# zook.net
KiCad netlist of a schematic drawn in EAGLE
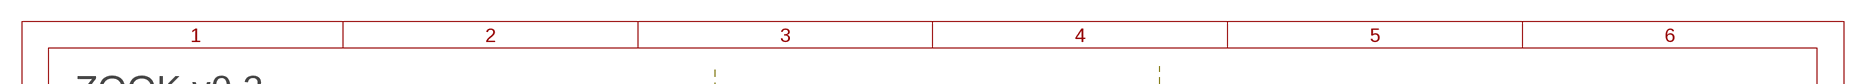
[diagram p0: schematic, sheet 1, part 1 of 2]
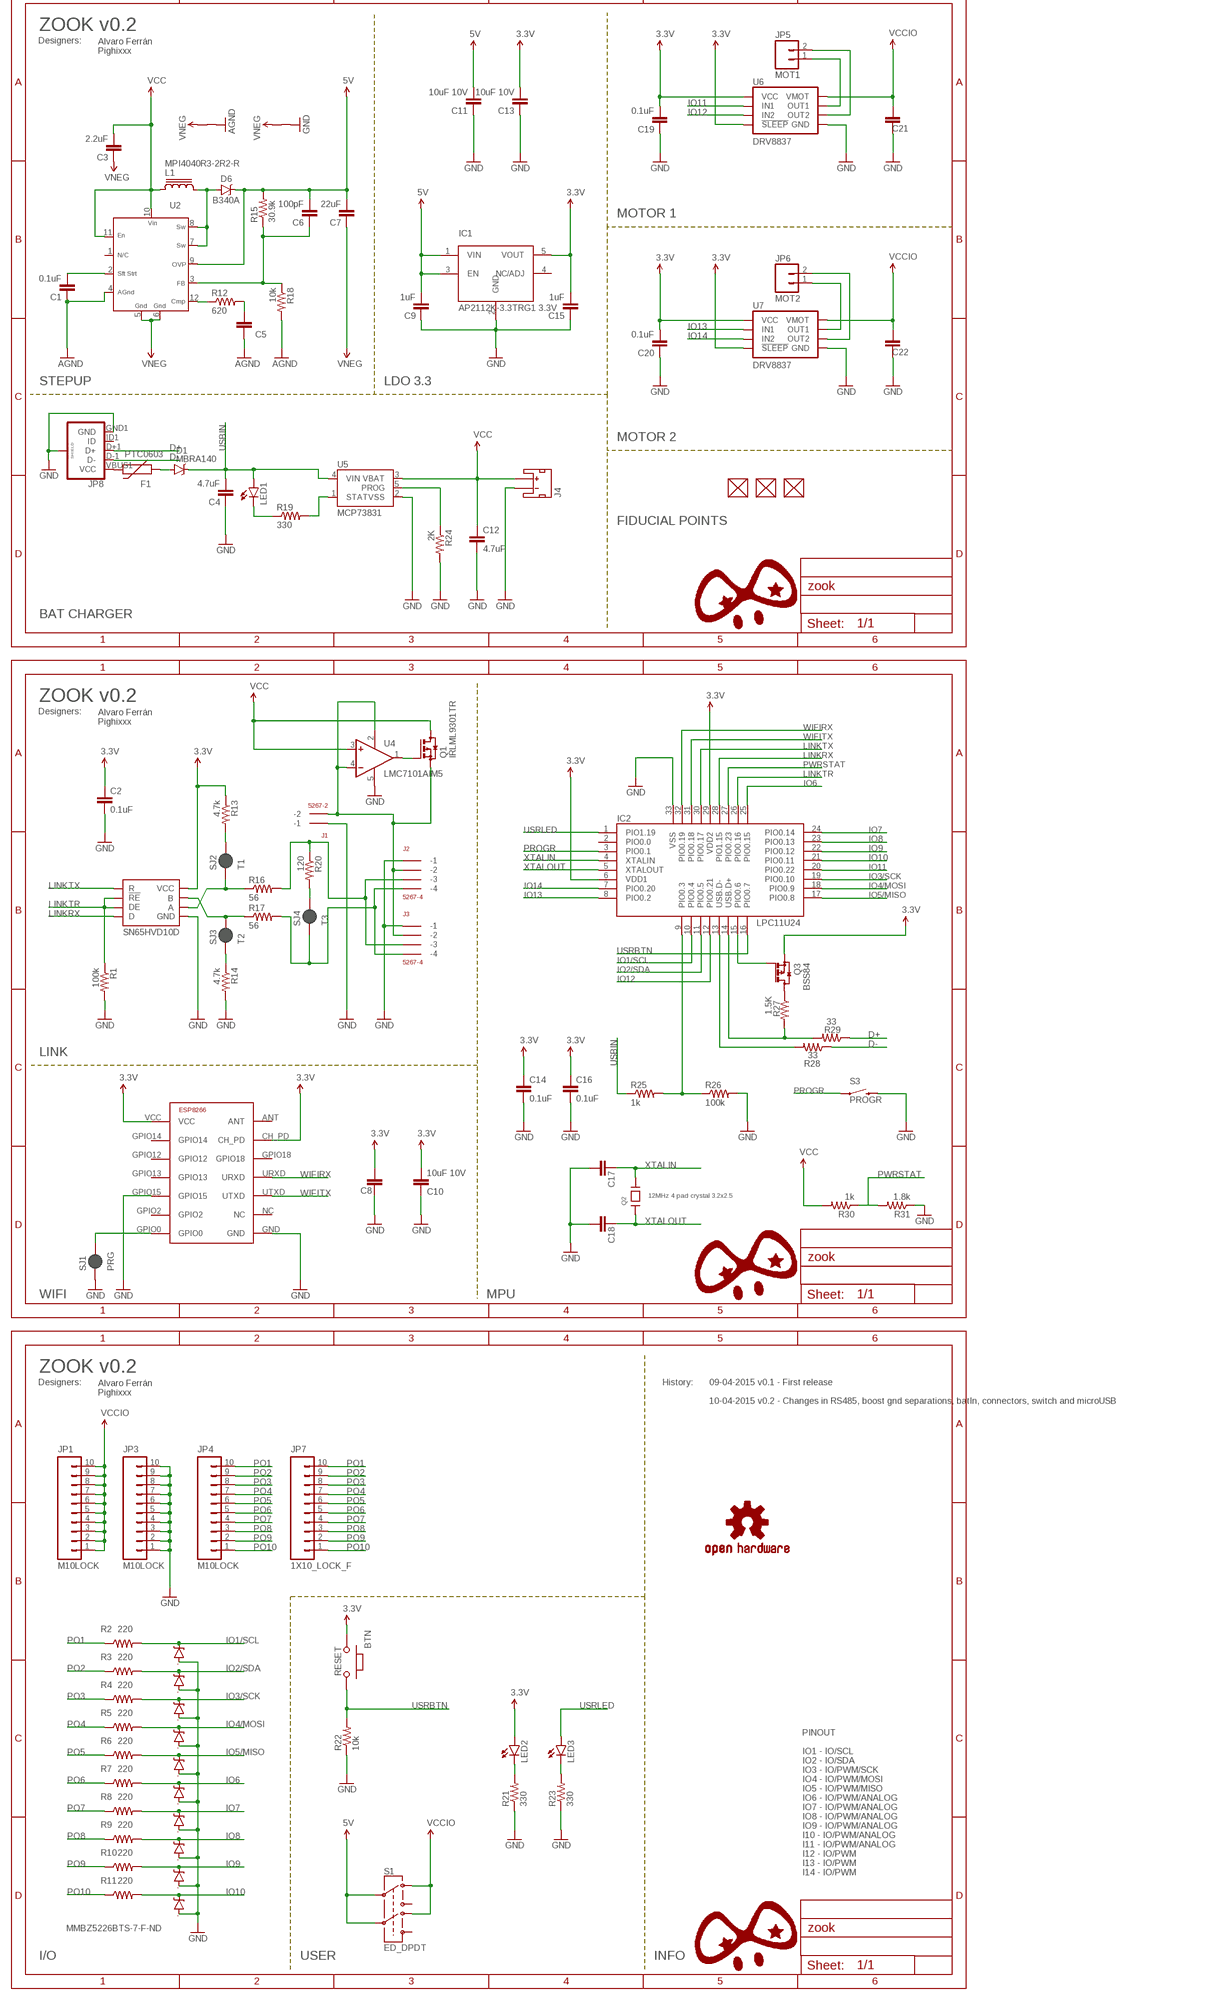
[diagram p1: schematic, sheet 1, part 2 of 2]

(export (version "E")
  (design (tool "Eeschema 10.0.6"))
  (components
    (comp (ref "BTN")
      (value "RESET")
      (footprint "eagle-import:157SW")
      (libsource (lib "eagle-import") (part "PB157"))
    )
    (comp (ref "C1")
      (value "0.1uF")
      (footprint "eagle-import:0402-CAP")
      (libsource (lib "eagle-import") (part "CAP0402-CAP"))
    )
    (comp (ref "C2")
      (value "0.1uF")
      (footprint "eagle-import:0402-CAP")
      (libsource (lib "eagle-import") (part "CAP0402-CAP"))
    )
    (comp (ref "C3")
      (value "2.2uF")
      (footprint "eagle-import:0402-CAP")
      (libsource (lib "eagle-import") (part "CAP0402-CAP"))
    )
    (comp (ref "C4")
      (value "4.7uF")
      (footprint "eagle-import:0402-CAP")
      (libsource (lib "eagle-import") (part "CAP0402-CAP"))
    )
    (comp (ref "C5")
      (value "10nF")
      (footprint "eagle-import:0402-CAP")
      (libsource (lib "eagle-import") (part "CAP0402-CAP"))
    )
    (comp (ref "C6")
      (value "100pF")
      (footprint "eagle-import:0402-CAP")
      (libsource (lib "eagle-import") (part "CAP0402-CAP"))
    )
    (comp (ref "C7")
      (value "22uF")
      (footprint "eagle-import:0805")
      (libsource (lib "eagle-import") (part "22UF-6.3V-20%(0805)"))
    )
    (comp (ref "C8")
      (value "0.1uF")
      (footprint "eagle-import:0402-CAP")
      (libsource (lib "eagle-import") (part "CAP0402-CAP"))
    )
    (comp (ref "C9")
      (value "1uF")
      (footprint "eagle-import:0402-CAP")
      (libsource (lib "eagle-import") (part "CAP0402-CAP"))
    )
    (comp (ref "C10")
      (value "10uF 10V")
      (footprint "eagle-import:0402-CAP")
      (libsource (lib "eagle-import") (part "CAP0402-CAP"))
    )
    (comp (ref "C11")
      (value "10uF 10V")
      (footprint "eagle-import:0402-CAP")
      (libsource (lib "eagle-import") (part "CAP0402-CAP"))
    )
    (comp (ref "C12")
      (value "4.7uF")
      (footprint "eagle-import:0402-CAP")
      (libsource (lib "eagle-import") (part "CAP0402-CAP"))
    )
    (comp (ref "C13")
      (value "10uF 10V")
      (footprint "eagle-import:0402-CAP")
      (libsource (lib "eagle-import") (part "CAP0402-CAP"))
    )
    (comp (ref "C14")
      (value "0.1uF")
      (footprint "eagle-import:0402-CAP")
      (libsource (lib "eagle-import") (part "CAP0402-CAP"))
    )
    (comp (ref "C15")
      (value "1uF")
      (footprint "eagle-import:0402-CAP")
      (libsource (lib "eagle-import") (part "CAP0402-CAP"))
    )
    (comp (ref "C16")
      (value "0.1uF")
      (footprint "eagle-import:0402-CAP")
      (libsource (lib "eagle-import") (part "CAP0402-CAP"))
    )
    (comp (ref "C17")
      (value "27pF")
      (footprint "eagle-import:0402-CAP")
      (libsource (lib "eagle-import") (part "CAP0402-CAP"))
    )
    (comp (ref "C18")
      (value "27pF")
      (footprint "eagle-import:0402-CAP")
      (libsource (lib "eagle-import") (part "CAP0402-CAP"))
    )
    (comp (ref "C19")
      (value "0.1uF")
      (footprint "eagle-import:0402-CAP")
      (libsource (lib "eagle-import") (part "CAP0402-CAP"))
    )
    (comp (ref "C20")
      (value "0.1uF")
      (footprint "eagle-import:0402-CAP")
      (libsource (lib "eagle-import") (part "CAP0402-CAP"))
    )
    (comp (ref "C21")
      (value "0.1uF")
      (footprint "eagle-import:0402-CAP")
      (libsource (lib "eagle-import") (part "CAP0402-CAP"))
    )
    (comp (ref "C22")
      (value "0.1uF")
      (footprint "eagle-import:0402-CAP")
      (libsource (lib "eagle-import") (part "CAP0402-CAP"))
    )
    (comp (ref "D1")
      (value "MBRA140")
      (footprint "eagle-import:SMA-DIODE")
      (libsource (lib "eagle-import") (part "MBRA140"))
    )
    (comp (ref "D2")
      (value "ZENERARRAY")
      (footprint "eagle-import:SOT363")
      (libsource (lib "eagle-import") (part "ZENERARRAY"))
    )
    (comp (ref "D3")
      (value "ZENERARRAY")
      (footprint "eagle-import:SOT363")
      (libsource (lib "eagle-import") (part "ZENERARRAY"))
    )
    (comp (ref "D4")
      (value "ZENERARRAY")
      (footprint "eagle-import:SOT363")
      (libsource (lib "eagle-import") (part "ZENERARRAY"))
    )
    (comp (ref "D5")
      (value "ZENERARRAY")
      (footprint "eagle-import:SOT363")
      (libsource (lib "eagle-import") (part "ZENERARRAY"))
    )
    (comp (ref "D6")
      (value "B340A")
      (footprint "eagle-import:SMA-DIODE")
      (libsource (lib "eagle-import") (part "DIODE-SCHOTTKY-B340A"))
    )
    (comp (ref "F1")
      (value "PTC0603")
      (footprint "eagle-import:0603")
      (libsource (lib "eagle-import") (part "PTC0603"))
    )
    (comp (ref "FUD1")
      (value "FIDUCIAL")
      (footprint "eagle-import:FIDUCIAL_40MIL")
      (libsource (lib "eagle-import") (part "FIDUCIAL"))
    )
    (comp (ref "FUD2")
      (value "FIDUCIAL")
      (footprint "eagle-import:FIDUCIAL_40MIL")
      (libsource (lib "eagle-import") (part "FIDUCIAL"))
    )
    (comp (ref "FUD3")
      (value "FIDUCIAL")
      (footprint "eagle-import:FIDUCIAL_40MIL")
      (libsource (lib "eagle-import") (part "FIDUCIAL"))
    )
    (comp (ref "GND5")
      (value "VIRTUAL_GND")
      (footprint "eagle-import:STARGND")
      (libsource (lib "eagle-import") (part "VIRTUAL_GND"))
    )
    (comp (ref "GND6")
      (value "VIRTUAL_GND")
      (footprint "eagle-import:STARGND")
      (libsource (lib "eagle-import") (part "VIRTUAL_GND"))
    )
    (comp (ref "IC1")
      (value "AP2112K-3.3TRG1 3.3V")
      (footprint "eagle-import:SOT23-5")
      (libsource (lib "eagle-import") (part "5PIN_REG"))
    )
    (comp (ref "IC2")
      (value "LPC11U24")
      (footprint "eagle-import:HVQFN33_5X5MM")
      (libsource (lib "eagle-import") (part "LPC11U2X_HVQFN33(5X5)"))
    )
    (comp (ref "J1")
      (value "5267-2")
      (footprint "eagle-import:5267-2")
      (libsource (lib "eagle-import") (part "5267-2"))
    )
    (comp (ref "J2")
      (value "5267-4")
      (footprint "eagle-import:5267-4")
      (libsource (lib "eagle-import") (part "5267-4"))
    )
    (comp (ref "J3")
      (value "5267-4")
      (footprint "eagle-import:5267-4")
      (libsource (lib "eagle-import") (part "5267-4"))
    )
    (comp (ref "J4")
      (value "BATT")
      (footprint "eagle-import:JST-2-SMD")
      (libsource (lib "eagle-import") (part "JST_2MM_MALE"))
    )
    (comp (ref "JP1")
      (value "M10LOCK")
      (footprint "eagle-import:1X10_LOCK")
      (libsource (lib "eagle-import") (part "M10LOCK"))
    )
    (comp (ref "JP3")
      (value "M10LOCK")
      (footprint "eagle-import:1X10_LOCK")
      (libsource (lib "eagle-import") (part "M10LOCK"))
    )
    (comp (ref "JP4")
      (value "M10LOCK")
      (footprint "eagle-import:1X10_LOCK")
      (libsource (lib "eagle-import") (part "M10LOCK"))
    )
    (comp (ref "JP5")
      (value "MOT1")
      (footprint "eagle-import:MOLEX-1X2")
      (libsource (lib "eagle-import") (part "M02POLAR"))
    )
    (comp (ref "JP6")
      (value "MOT2")
      (footprint "eagle-import:MOLEX-1X2")
      (libsource (lib "eagle-import") (part "M02POLAR"))
    )
    (comp (ref "JP7")
      (value "1X10_LOCK_F")
      (footprint "eagle-import:1X10_LOCK_F")
      (libsource (lib "eagle-import") (part "1X10_LOCK_F"))
    )
    (comp (ref "JP8")
      (value "USB_MICROB_PLUGCONN-11752")
      (footprint "eagle-import:USB-B-MICRO-SMD_V03")
      (libsource (lib "eagle-import") (part "USB_MICROB_PLUGCONN-11752"))
    )
    (comp (ref "L1")
      (value "MPI4040R3-2R2-R")
      (footprint "eagle-import:MPI4040R3-2R2-R")
      (libsource (lib "eagle-import") (part "MPI4040R3-2R2-R"))
    )
    (comp (ref "LED1")
      (value "LED0603")
      (footprint "eagle-import:LED-0603")
      (libsource (lib "eagle-import") (part "LED0603"))
    )
    (comp (ref "LED2")
      (value "LED0603")
      (footprint "eagle-import:LED-0603")
      (libsource (lib "eagle-import") (part "LED0603"))
    )
    (comp (ref "LED3")
      (value "LED0603")
      (footprint "eagle-import:LED-0603")
      (libsource (lib "eagle-import") (part "LED0603"))
    )
    (comp (ref "LOGO3")
      (value "OSHW-LOGOS")
      (footprint "eagle-import:OSHW-LOGO-S")
      (libsource (lib "eagle-import") (part "OSHW-LOGOS"))
    )
    (comp (ref "Q1")
      (value "IRLML9301TR")
      (footprint "eagle-import:SOT23")
      (libsource (lib "eagle-import") (part "BSS84"))
    )
    (comp (ref "Q2")
      (value "12MHz 4 pad crystal 3.2x2.5")
      (footprint "eagle-import:CRYSTAL_3.2X2.5")
      (libsource (lib "eagle-import") (part "CRYSTAL3.2X2.5"))
    )
    (comp (ref "Q3")
      (value "BSS84")
      (footprint "eagle-import:SOT23")
      (libsource (lib "eagle-import") (part "BSS84"))
    )
    (comp (ref "R1")
      (value "100k")
      (footprint "eagle-import:0402-RES")
      (libsource (lib "eagle-import") (part "RESISTOR0402-RES"))
    )
    (comp (ref "R2")
      (value "220")
      (footprint "eagle-import:0603-RES")
      (libsource (lib "eagle-import") (part "220KOHM1/10W1%(0603)"))
    )
    (comp (ref "R3")
      (value "220")
      (footprint "eagle-import:0603-RES")
      (libsource (lib "eagle-import") (part "220KOHM1/10W1%(0603)"))
    )
    (comp (ref "R4")
      (value "220")
      (footprint "eagle-import:0603-RES")
      (libsource (lib "eagle-import") (part "220KOHM1/10W1%(0603)"))
    )
    (comp (ref "R5")
      (value "220")
      (footprint "eagle-import:0603-RES")
      (libsource (lib "eagle-import") (part "220KOHM1/10W1%(0603)"))
    )
    (comp (ref "R6")
      (value "220")
      (footprint "eagle-import:0603-RES")
      (libsource (lib "eagle-import") (part "220KOHM1/10W1%(0603)"))
    )
    (comp (ref "R7")
      (value "220")
      (footprint "eagle-import:0603-RES")
      (libsource (lib "eagle-import") (part "220KOHM1/10W1%(0603)"))
    )
    (comp (ref "R8")
      (value "220")
      (footprint "eagle-import:0603-RES")
      (libsource (lib "eagle-import") (part "220KOHM1/10W1%(0603)"))
    )
    (comp (ref "R9")
      (value "220")
      (footprint "eagle-import:0603-RES")
      (libsource (lib "eagle-import") (part "220KOHM1/10W1%(0603)"))
    )
    (comp (ref "R10")
      (value "220")
      (footprint "eagle-import:0603-RES")
      (libsource (lib "eagle-import") (part "220KOHM1/10W1%(0603)"))
    )
    (comp (ref "R11")
      (value "220")
      (footprint "eagle-import:0603-RES")
      (libsource (lib "eagle-import") (part "220KOHM1/10W1%(0603)"))
    )
    (comp (ref "R12")
      (value "620")
      (footprint "eagle-import:0402-RES")
      (libsource (lib "eagle-import") (part "RESISTOR0402-RES"))
    )
    (comp (ref "R13")
      (value "4.7k")
      (footprint "eagle-import:0402-RES")
      (libsource (lib "eagle-import") (part "RESISTOR0402-RES"))
    )
    (comp (ref "R14")
      (value "4.7k")
      (footprint "eagle-import:0402-RES")
      (libsource (lib "eagle-import") (part "RESISTOR0402-RES"))
    )
    (comp (ref "R15")
      (value "30.9k")
      (footprint "eagle-import:0402-RES")
      (libsource (lib "eagle-import") (part "RESISTOR0402-RES"))
    )
    (comp (ref "R16")
      (value "56")
      (footprint "eagle-import:0402-RES")
      (libsource (lib "eagle-import") (part "RESISTOR0402-RES"))
    )
    (comp (ref "R17")
      (value "56")
      (footprint "eagle-import:0402-RES")
      (libsource (lib "eagle-import") (part "RESISTOR0402-RES"))
    )
    (comp (ref "R18")
      (value "10k")
      (footprint "eagle-import:0402-RES")
      (libsource (lib "eagle-import") (part "RESISTOR0402-RES"))
    )
    (comp (ref "R19")
      (value "330")
      (footprint "eagle-import:0402-RES")
      (libsource (lib "eagle-import") (part "RESISTOR0402-RES"))
    )
    (comp (ref "R20")
      (value "120")
      (footprint "eagle-import:0402-RES")
      (libsource (lib "eagle-import") (part "RESISTOR0402-RES"))
    )
    (comp (ref "R21")
      (value "330")
      (footprint "eagle-import:0402-RES")
      (libsource (lib "eagle-import") (part "RESISTOR0402-RES"))
    )
    (comp (ref "R22")
      (value "10k")
      (footprint "eagle-import:0402-RES")
      (libsource (lib "eagle-import") (part "RESISTOR0402-RES"))
    )
    (comp (ref "R23")
      (value "330")
      (footprint "eagle-import:0402-RES")
      (libsource (lib "eagle-import") (part "RESISTOR0402-RES"))
    )
    (comp (ref "R24")
      (value "2K")
      (footprint "eagle-import:0402-RES")
      (libsource (lib "eagle-import") (part "RESISTOR0402-RES"))
    )
    (comp (ref "R25")
      (value "1k")
      (footprint "eagle-import:0402-RES")
      (libsource (lib "eagle-import") (part "RESISTOR0402-RES"))
    )
    (comp (ref "R26")
      (value "100k")
      (footprint "eagle-import:0402-RES")
      (libsource (lib "eagle-import") (part "RESISTOR0402-RES"))
    )
    (comp (ref "R27")
      (value "1.5K")
      (footprint "eagle-import:0402-RES")
      (libsource (lib "eagle-import") (part "RESISTOR0402-RES"))
    )
    (comp (ref "R28")
      (value "33")
      (footprint "eagle-import:0402-RES")
      (libsource (lib "eagle-import") (part "RESISTOR0402-RES"))
    )
    (comp (ref "R29")
      (value "33")
      (footprint "eagle-import:0402-RES")
      (libsource (lib "eagle-import") (part "RESISTOR0402-RES"))
    )
    (comp (ref "R30")
      (value "1k")
      (footprint "eagle-import:0402-RES")
      (libsource (lib "eagle-import") (part "RESISTOR0402-RES"))
    )
    (comp (ref "R31")
      (value "1.8k")
      (footprint "eagle-import:0402-RES")
      (libsource (lib "eagle-import") (part "RESISTOR0402-RES"))
    )
    (comp (ref "S1")
      (value "ED_DPDT")
      (footprint "eagle-import:ED_DPDT")
      (libsource (lib "eagle-import") (part "ED_DPDT"))
    )
    (comp (ref "S3")
      (value "PROGR")
      (footprint "eagle-import:TACTILE-PTH-SIDEEZ")
      (libsource (lib "eagle-import") (part "SWITCH-MOMENTARY-2SIDE_EZ"))
    )
    (comp (ref "SJ1")
      (value "PRG")
      (footprint "eagle-import:PAD-JUMPER-2-NC_BY_PASTE_YES_SILK")
      (libsource (lib "eagle-import") (part "JUMPER-PAD-2-NC_BY_PASTE"))
    )
    (comp (ref "SJ2")
      (value "T1")
      (footprint "eagle-import:PAD-JUMPER-2-NC_BY_PASTE_YES_SILK")
      (libsource (lib "eagle-import") (part "JUMPER-PAD-2-NC_BY_PASTE"))
    )
    (comp (ref "SJ3")
      (value "T2")
      (footprint "eagle-import:PAD-JUMPER-2-NC_BY_PASTE_YES_SILK")
      (libsource (lib "eagle-import") (part "JUMPER-PAD-2-NC_BY_PASTE"))
    )
    (comp (ref "SJ4")
      (value "T3")
      (footprint "eagle-import:PAD-JUMPER-2-NC_BY_PASTE_YES_SILK")
      (libsource (lib "eagle-import") (part "JUMPER-PAD-2-NC_BY_PASTE"))
    )
    (comp (ref "U2")
      (value "MIC2253")
      (footprint "eagle-import:MLF12_3.0MM_X_3.0MM")
      (libsource (lib "eagle-import") (part "MIC2253"))
    )
    (comp (ref "U3")
      (value "ESP8266")
      (footprint "eagle-import:ESP-03")
      (libsource (lib "eagle-import") (part "ESP8266"))
    )
    (comp (ref "U4")
      (value "LMC7101AIM5")
      (footprint "eagle-import:SOT23-5")
      (libsource (lib "eagle-import") (part "LMC7101AIM5"))
    )
    (comp (ref "U5")
      (value "MCP73831")
      (footprint "eagle-import:SOT23-5")
      (libsource (lib "eagle-import") (part "MCP73831"))
    )
    (comp (ref "U6")
      (value "DRV8837")
      (footprint "eagle-import:DSG")
      (libsource (lib "eagle-import") (part "DRV8837"))
    )
    (comp (ref "U7")
      (value "DRV8837")
      (footprint "eagle-import:DSG")
      (libsource (lib "eagle-import") (part "DRV8837"))
    )
    (comp (ref "U8")
      (value "SN65HVD10D")
      (footprint "eagle-import:SO08")
      (libsource (lib "eagle-import") (part "SN65HVD10D"))
    )
  )
  (nets
    (net (code "1") (name "/D+") (class "Default")
      (node (ref "JP8") (pin "D+1") (pinfunction "D+_D+1") (pintype "bidirectional"))
      (node (ref "R29") (pin "1") (pinfunction "1_1") (pintype "passive"))
    )
    (net (code "2") (name "/D-") (class "Default")
      (node (ref "JP8") (pin "D-1") (pinfunction "D-_D-1") (pintype "bidirectional"))
      (node (ref "R28") (pin "1") (pinfunction "1_1") (pintype "passive"))
    )
    (net (code "3") (name "/IO1{slash}SCL") (class "Default")
      (node (ref "D2") (pin "6") (pinfunction "C_6") (pintype "passive"))
      (node (ref "IC2") (pin "10") (pinfunction "PIO0.4_10") (pintype "bidirectional"))
      (node (ref "R2") (pin "2") (pinfunction "2_2") (pintype "passive"))
    )
    (net (code "4") (name "/IO2{slash}SDA") (class "Default")
      (node (ref "D2") (pin "5") (pinfunction "C_5") (pintype "passive"))
      (node (ref "IC2") (pin "11") (pinfunction "PIO0.5_11") (pintype "bidirectional"))
      (node (ref "R3") (pin "2") (pinfunction "2_2") (pintype "passive"))
    )
    (net (code "5") (name "/IO3{slash}SCK") (class "Default")
      (node (ref "D2") (pin "4") (pinfunction "C_4") (pintype "passive"))
      (node (ref "IC2") (pin "19") (pinfunction "PIO0.10_19") (pintype "bidirectional"))
      (node (ref "R4") (pin "2") (pinfunction "2_2") (pintype "passive"))
    )
    (net (code "6") (name "/IO4{slash}MOSI") (class "Default")
      (node (ref "D3") (pin "6") (pinfunction "C_6") (pintype "passive"))
      (node (ref "IC2") (pin "18") (pinfunction "PIO0.9_18") (pintype "bidirectional"))
      (node (ref "R5") (pin "2") (pinfunction "2_2") (pintype "passive"))
    )
    (net (code "7") (name "/IO5{slash}MISO") (class "Default")
      (node (ref "D3") (pin "5") (pinfunction "C_5") (pintype "passive"))
      (node (ref "IC2") (pin "17") (pinfunction "PIO0.8_17") (pintype "bidirectional"))
      (node (ref "R6") (pin "2") (pinfunction "2_2") (pintype "passive"))
    )
    (net (code "8") (name "/IO6") (class "Default")
      (node (ref "D3") (pin "4") (pinfunction "C_4") (pintype "passive"))
      (node (ref "IC2") (pin "25") (pinfunction "PIO0.15_25") (pintype "bidirectional"))
      (node (ref "R7") (pin "2") (pinfunction "2_2") (pintype "passive"))
    )
    (net (code "9") (name "/IO7") (class "Default")
      (node (ref "D4") (pin "6") (pinfunction "C_6") (pintype "passive"))
      (node (ref "IC2") (pin "24") (pinfunction "PIO0.14_24") (pintype "bidirectional"))
      (node (ref "R8") (pin "2") (pinfunction "2_2") (pintype "passive"))
    )
    (net (code "10") (name "/IO8") (class "Default")
      (node (ref "D4") (pin "5") (pinfunction "C_5") (pintype "passive"))
      (node (ref "IC2") (pin "23") (pinfunction "PIO0.13_23") (pintype "bidirectional"))
      (node (ref "R9") (pin "2") (pinfunction "2_2") (pintype "passive"))
    )
    (net (code "11") (name "/IO9") (class "Default")
      (node (ref "D4") (pin "4") (pinfunction "C_4") (pintype "passive"))
      (node (ref "IC2") (pin "22") (pinfunction "PIO0.12_22") (pintype "bidirectional"))
      (node (ref "R10") (pin "2") (pinfunction "2_2") (pintype "passive"))
    )
    (net (code "12") (name "/IO10") (class "Default")
      (node (ref "D5") (pin "6") (pinfunction "C_6") (pintype "passive"))
      (node (ref "IC2") (pin "21") (pinfunction "PIO0.11_21") (pintype "bidirectional"))
      (node (ref "R11") (pin "2") (pinfunction "2_2") (pintype "passive"))
    )
    (net (code "13") (name "/IO11") (class "Default")
      (node (ref "IC2") (pin "20") (pinfunction "PIO0.22_20") (pintype "bidirectional"))
      (node (ref "U6") (pin "6") (pinfunction "IN1_6") (pintype "bidirectional"))
    )
    (net (code "14") (name "/IO12") (class "Default")
      (node (ref "IC2") (pin "12") (pinfunction "PIO0.21_12") (pintype "bidirectional"))
      (node (ref "U6") (pin "5") (pinfunction "IN2_5") (pintype "bidirectional"))
    )
    (net (code "15") (name "/IO13") (class "Default")
      (node (ref "IC2") (pin "8") (pinfunction "PIO0.2_8") (pintype "bidirectional"))
      (node (ref "U7") (pin "6") (pinfunction "IN1_6") (pintype "bidirectional"))
    )
    (net (code "16") (name "/IO14") (class "Default")
      (node (ref "IC2") (pin "7") (pinfunction "PIO0.20_7") (pintype "bidirectional"))
      (node (ref "U7") (pin "5") (pinfunction "IN2_5") (pintype "bidirectional"))
    )
    (net (code "17") (name "/LINKRX") (class "Default")
      (node (ref "IC2") (pin "28") (pinfunction "PIO1.15_28") (pintype "bidirectional"))
      (node (ref "U8") (pin "4") (pinfunction "P$4_4") (pintype "bidirectional"))
    )
    (net (code "18") (name "/LINKTR") (class "Default")
      (node (ref "IC2") (pin "26") (pinfunction "PIO0.16_26") (pintype "bidirectional"))
      (node (ref "R1") (pin "1") (pinfunction "1_1") (pintype "passive"))
      (node (ref "U8") (pin "2") (pinfunction "P$2_2") (pintype "bidirectional"))
      (node (ref "U8") (pin "3") (pinfunction "P$3_3") (pintype "bidirectional"))
    )
    (net (code "19") (name "/LINKTX") (class "Default")
      (node (ref "IC2") (pin "30") (pinfunction "PIO0.17_30") (pintype "bidirectional"))
      (node (ref "U8") (pin "1") (pinfunction "P$1_1") (pintype "bidirectional"))
    )
    (net (code "20") (name "/PO1") (class "Default")
      (node (ref "JP4") (pin "10") (pinfunction "10_10") (pintype "passive"))
      (node (ref "JP7") (pin "10") (pinfunction "10_10") (pintype "passive"))
      (node (ref "R2") (pin "1") (pinfunction "1_1") (pintype "passive"))
    )
    (net (code "21") (name "/PO2") (class "Default")
      (node (ref "JP4") (pin "9") (pinfunction "9_9") (pintype "passive"))
      (node (ref "JP7") (pin "9") (pinfunction "9_9") (pintype "passive"))
      (node (ref "R3") (pin "1") (pinfunction "1_1") (pintype "passive"))
    )
    (net (code "22") (name "/PO3") (class "Default")
      (node (ref "JP4") (pin "8") (pinfunction "8_8") (pintype "passive"))
      (node (ref "JP7") (pin "8") (pinfunction "8_8") (pintype "passive"))
      (node (ref "R4") (pin "1") (pinfunction "1_1") (pintype "passive"))
    )
    (net (code "23") (name "/PO4") (class "Default")
      (node (ref "JP4") (pin "7") (pinfunction "7_7") (pintype "passive"))
      (node (ref "JP7") (pin "7") (pinfunction "7_7") (pintype "passive"))
      (node (ref "R5") (pin "1") (pinfunction "1_1") (pintype "passive"))
    )
    (net (code "24") (name "/PO5") (class "Default")
      (node (ref "JP4") (pin "6") (pinfunction "6_6") (pintype "passive"))
      (node (ref "JP7") (pin "6") (pinfunction "6_6") (pintype "passive"))
      (node (ref "R6") (pin "1") (pinfunction "1_1") (pintype "passive"))
    )
    (net (code "25") (name "/PO6") (class "Default")
      (node (ref "JP4") (pin "5") (pinfunction "5_5") (pintype "passive"))
      (node (ref "JP7") (pin "5") (pinfunction "5_5") (pintype "passive"))
      (node (ref "R7") (pin "1") (pinfunction "1_1") (pintype "passive"))
    )
    (net (code "26") (name "/PO7") (class "Default")
      (node (ref "JP4") (pin "4") (pinfunction "4_4") (pintype "passive"))
      (node (ref "JP7") (pin "4") (pinfunction "4_4") (pintype "passive"))
      (node (ref "R8") (pin "1") (pinfunction "1_1") (pintype "passive"))
    )
    (net (code "27") (name "/PO8") (class "Default")
      (node (ref "JP4") (pin "3") (pinfunction "3_3") (pintype "passive"))
      (node (ref "JP7") (pin "3") (pinfunction "3_3") (pintype "passive"))
      (node (ref "R9") (pin "1") (pinfunction "1_1") (pintype "passive"))
    )
    (net (code "28") (name "/PO9") (class "Default")
      (node (ref "JP4") (pin "2") (pinfunction "2_2") (pintype "passive"))
      (node (ref "JP7") (pin "2") (pinfunction "2_2") (pintype "passive"))
      (node (ref "R10") (pin "1") (pinfunction "1_1") (pintype "passive"))
    )
    (net (code "29") (name "/PO10") (class "Default")
      (node (ref "JP4") (pin "1") (pinfunction "1_1") (pintype "passive"))
      (node (ref "JP7") (pin "1") (pinfunction "1_1") (pintype "passive"))
      (node (ref "R11") (pin "1") (pinfunction "1_1") (pintype "passive"))
    )
    (net (code "30") (name "/PROGR") (class "Default")
      (node (ref "IC2") (pin "3") (pinfunction "PIO0.1_3") (pintype "bidirectional"))
      (node (ref "S3") (pin "1") (pinfunction "1_1") (pintype "passive"))
    )
    (net (code "31") (name "/PWRSTAT") (class "Default")
      (node (ref "IC2") (pin "27") (pinfunction "PIO0.23_27") (pintype "bidirectional"))
      (node (ref "R30") (pin "1") (pinfunction "1_1") (pintype "passive"))
      (node (ref "R31") (pin "2") (pinfunction "2_2") (pintype "passive"))
    )
    (net (code "32") (name "/USBIN") (class "Default")
      (node (ref "C4") (pin "2") (pinfunction "2_2") (pintype "passive"))
      (node (ref "D1") (pin "C") (pinfunction "C_C") (pintype "passive"))
      (node (ref "LED1") (pin "A") (pinfunction "A_A") (pintype "passive"))
      (node (ref "R25") (pin "1") (pinfunction "1_1") (pintype "passive"))
      (node (ref "U5") (pin "4") (pinfunction "VIN_4") (pintype "power_in"))
    )
    (net (code "33") (name "/USRBTN") (class "Default")
      (node (ref "BTN") (pin "2") (pinfunction "2_2") (pintype "passive"))
      (node (ref "IC2") (pin "16") (pinfunction "PIO0.7_16") (pintype "bidirectional"))
      (node (ref "R22") (pin "2") (pinfunction "2_2") (pintype "passive"))
    )
    (net (code "34") (name "/USRLED") (class "Default")
      (node (ref "IC2") (pin "1") (pinfunction "PIO1.19_1") (pintype "bidirectional"))
      (node (ref "LED3") (pin "A") (pinfunction "A_A") (pintype "passive"))
    )
    (net (code "35") (name "/WIFIRX") (class "Default")
      (node (ref "IC2") (pin "32") (pinfunction "PIO0.19_32") (pintype "bidirectional"))
      (node (ref "U3") (pin "URXD") (pinfunction "URXD_URXD") (pintype "bidirectional"))
    )
    (net (code "36") (name "/WIFITX") (class "Default")
      (node (ref "IC2") (pin "31") (pinfunction "PIO0.18_31") (pintype "bidirectional"))
      (node (ref "U3") (pin "UTXD") (pinfunction "UTXD_UTXD") (pintype "bidirectional"))
    )
    (net (code "37") (name "/XTALIN") (class "Default")
      (node (ref "C17") (pin "1") (pinfunction "1_1") (pintype "passive"))
      (node (ref "IC2") (pin "4") (pinfunction "XTALIN_4") (pintype "bidirectional"))
      (node (ref "Q2") (pin "3") (pinfunction "P$2_3") (pintype "passive"))
    )
    (net (code "38") (name "/XTALOUT") (class "Default")
      (node (ref "C18") (pin "1") (pinfunction "1_1") (pintype "passive"))
      (node (ref "IC2") (pin "5") (pinfunction "XTALOUT_5") (pintype "bidirectional"))
      (node (ref "Q2") (pin "1") (pinfunction "P$1_1") (pintype "passive"))
    )
    (net (code "39") (name "3.3V") (class "Default")
      (node (ref "BTN") (pin "1") (pinfunction "1_1") (pintype "passive"))
      (node (ref "C10") (pin "2") (pinfunction "2_2") (pintype "passive"))
      (node (ref "C13") (pin "2") (pinfunction "2_2") (pintype "passive"))
      (node (ref "C14") (pin "1") (pinfunction "1_1") (pintype "passive"))
      (node (ref "C15") (pin "2") (pinfunction "2_2") (pintype "passive"))
      (node (ref "C16") (pin "1") (pinfunction "1_1") (pintype "passive"))
      (node (ref "C19") (pin "2") (pinfunction "2_2") (pintype "passive"))
      (node (ref "C2") (pin "1") (pinfunction "1_1") (pintype "passive"))
      (node (ref "C20") (pin "2") (pinfunction "2_2") (pintype "passive"))
      (node (ref "C8") (pin "2") (pinfunction "2_2") (pintype "passive"))
      (node (ref "IC1") (pin "5") (pinfunction "VOUT_5") (pintype "bidirectional"))
      (node (ref "IC2") (pin "29") (pinfunction "VDD2_29") (pintype "bidirectional"))
      (node (ref "IC2") (pin "6") (pinfunction "VDD1_6") (pintype "bidirectional"))
      (node (ref "LED2") (pin "A") (pinfunction "A_A") (pintype "passive"))
      (node (ref "Q3") (pin "2") (pinfunction "S_2") (pintype "passive"))
      (node (ref "R13") (pin "1") (pinfunction "1_1") (pintype "passive"))
      (node (ref "U3") (pin "CH_PD") (pinfunction "CH_PD_CH_PD") (pintype "bidirectional"))
      (node (ref "U3") (pin "VCC") (pinfunction "VCC_VCC") (pintype "bidirectional"))
      (node (ref "U6") (pin "7") (pinfunction "~{SLEEP}_7") (pintype "bidirectional"))
      (node (ref "U6") (pin "8") (pinfunction "VCC_8") (pintype "bidirectional"))
      (node (ref "U7") (pin "7") (pinfunction "~{SLEEP}_7") (pintype "bidirectional"))
      (node (ref "U7") (pin "8") (pinfunction "VCC_8") (pintype "bidirectional"))
      (node (ref "U8") (pin "8") (pinfunction "P$8_8") (pintype "bidirectional"))
    )
    (net (code "40") (name "5V") (class "Default")
      (node (ref "C11") (pin "2") (pinfunction "2_2") (pintype "passive"))
      (node (ref "C6") (pin "2") (pinfunction "2_2") (pintype "passive"))
      (node (ref "C7") (pin "2") (pinfunction "2_2") (pintype "passive"))
      (node (ref "C9") (pin "2") (pinfunction "2_2") (pintype "passive"))
      (node (ref "D6") (pin "C") (pinfunction "C_C") (pintype "passive"))
      (node (ref "IC1") (pin "1") (pinfunction "VIN_1") (pintype "bidirectional"))
      (node (ref "IC1") (pin "3") (pinfunction "EN_3") (pintype "bidirectional"))
      (node (ref "R15") (pin "2") (pinfunction "2_2") (pintype "passive"))
      (node (ref "S1") (pin "2") (pinfunction "2_2") (pintype "bidirectional"))
      (node (ref "S1") (pin "5") (pinfunction "5_5") (pintype "bidirectional"))
      (node (ref "U2") (pin "9") (pinfunction "OVP_9") (pintype "passive"))
    )
    (net (code "41") (name "AGND") (class "Default")
      (node (ref "C1") (pin "1") (pinfunction "1_1") (pintype "passive"))
      (node (ref "C5") (pin "1") (pinfunction "1_1") (pintype "passive"))
      (node (ref "GND5") (pin "P$2") (pinfunction "P$2_P$2") (pintype "bidirectional"))
      (node (ref "R18") (pin "2") (pinfunction "2_2") (pintype "passive"))
      (node (ref "U2") (pin "4") (pinfunction "AGND_4") (pintype "passive"))
    )
    (net (code "42") (name "GND") (class "Default")
      (node (ref "C10") (pin "1") (pinfunction "1_1") (pintype "passive"))
      (node (ref "C11") (pin "1") (pinfunction "1_1") (pintype "passive"))
      (node (ref "C12") (pin "2") (pinfunction "2_2") (pintype "passive"))
      (node (ref "C13") (pin "1") (pinfunction "1_1") (pintype "passive"))
      (node (ref "C14") (pin "2") (pinfunction "2_2") (pintype "passive"))
      (node (ref "C15") (pin "1") (pinfunction "1_1") (pintype "passive"))
      (node (ref "C16") (pin "2") (pinfunction "2_2") (pintype "passive"))
      (node (ref "C17") (pin "2") (pinfunction "2_2") (pintype "passive"))
      (node (ref "C18") (pin "2") (pinfunction "2_2") (pintype "passive"))
      (node (ref "C19") (pin "1") (pinfunction "1_1") (pintype "passive"))
      (node (ref "C2") (pin "2") (pinfunction "2_2") (pintype "passive"))
      (node (ref "C20") (pin "1") (pinfunction "1_1") (pintype "passive"))
      (node (ref "C21") (pin "1") (pinfunction "1_1") (pintype "passive"))
      (node (ref "C22") (pin "1") (pinfunction "1_1") (pintype "passive"))
      (node (ref "C4") (pin "1") (pinfunction "1_1") (pintype "passive"))
      (node (ref "C8") (pin "1") (pinfunction "1_1") (pintype "passive"))
      (node (ref "C9") (pin "1") (pinfunction "1_1") (pintype "passive"))
      (node (ref "D2") (pin "1") (pinfunction "A_1") (pintype "passive"))
      (node (ref "D2") (pin "2") (pinfunction "A_2") (pintype "passive"))
      (node (ref "D2") (pin "3") (pinfunction "A_3") (pintype "passive"))
      (node (ref "D3") (pin "1") (pinfunction "A_1") (pintype "passive"))
      (node (ref "D3") (pin "2") (pinfunction "A_2") (pintype "passive"))
      (node (ref "D3") (pin "3") (pinfunction "A_3") (pintype "passive"))
      (node (ref "D4") (pin "1") (pinfunction "A_1") (pintype "passive"))
      (node (ref "D4") (pin "2") (pinfunction "A_2") (pintype "passive"))
      (node (ref "D4") (pin "3") (pinfunction "A_3") (pintype "passive"))
      (node (ref "D5") (pin "1") (pinfunction "A_1") (pintype "passive"))
      (node (ref "GND6") (pin "P$2") (pinfunction "P$2_P$2") (pintype "bidirectional"))
      (node (ref "IC1") (pin "2") (pinfunction "GND_2") (pintype "bidirectional"))
      (node (ref "IC2") (pin "33") (pinfunction "VSS_33") (pintype "bidirectional"))
      (node (ref "J1") (pin "P$1") (pinfunction "-1_P$1") (pintype "bidirectional"))
      (node (ref "J2") (pin "P$1") (pinfunction "-1_P$1") (pintype "bidirectional"))
      (node (ref "J3") (pin "P$1") (pinfunction "-1_P$1") (pintype "bidirectional"))
      (node (ref "J4") (pin "1") (pinfunction "-_1") (pintype "bidirectional"))
      (node (ref "JP3") (pin "1") (pinfunction "1_1") (pintype "passive"))
      (node (ref "JP3") (pin "10") (pinfunction "10_10") (pintype "passive"))
      (node (ref "JP3") (pin "2") (pinfunction "2_2") (pintype "passive"))
      (node (ref "JP3") (pin "3") (pinfunction "3_3") (pintype "passive"))
      (node (ref "JP3") (pin "4") (pinfunction "4_4") (pintype "passive"))
      (node (ref "JP3") (pin "5") (pinfunction "5_5") (pintype "passive"))
      (node (ref "JP3") (pin "6") (pinfunction "6_6") (pintype "passive"))
      (node (ref "JP3") (pin "7") (pinfunction "7_7") (pintype "passive"))
      (node (ref "JP3") (pin "8") (pinfunction "8_8") (pintype "passive"))
      (node (ref "JP3") (pin "9") (pinfunction "9_9") (pintype "passive"))
      (node (ref "JP8") (pin "GND1") (pinfunction "GND_GND1") (pintype "bidirectional"))
      (node (ref "JP8") (pin "SHIELD1") (pinfunction "SHIELD_SHIELD1") (pintype "bidirectional"))
      (node (ref "JP8") (pin "SHIELD2") (pinfunction "SHIELD_SHIELD2") (pintype "bidirectional"))
      (node (ref "JP8") (pin "SHIELD3") (pinfunction "SHIELD_SHIELD3") (pintype "bidirectional"))
      (node (ref "R1") (pin "2") (pinfunction "2_2") (pintype "passive"))
      (node (ref "R14") (pin "2") (pinfunction "2_2") (pintype "passive"))
      (node (ref "R21") (pin "1") (pinfunction "1_1") (pintype "passive"))
      (node (ref "R22") (pin "1") (pinfunction "1_1") (pintype "passive"))
      (node (ref "R23") (pin "1") (pinfunction "1_1") (pintype "passive"))
      (node (ref "R24") (pin "2") (pinfunction "2_2") (pintype "passive"))
      (node (ref "R26") (pin "2") (pinfunction "2_2") (pintype "passive"))
      (node (ref "R31") (pin "1") (pinfunction "1_1") (pintype "passive"))
      (node (ref "S3") (pin "2") (pinfunction "2_2") (pintype "passive"))
      (node (ref "SJ1") (pin "1") (pinfunction "1_1") (pintype "passive"))
      (node (ref "U3") (pin "GND") (pinfunction "GND_GND") (pintype "bidirectional"))
      (node (ref "U3") (pin "GPIO15") (pinfunction "GPIO15_GPIO15") (pintype "bidirectional"))
      (node (ref "U4") (pin "5") (pinfunction "V-_5") (pintype "power_in"))
      (node (ref "U5") (pin "2") (pinfunction "VSS_2") (pintype "power_in"))
      (node (ref "U6") (pin "4") (pinfunction "GND_4") (pintype "bidirectional"))
      (node (ref "U6") (pin "PAD") (pinfunction "GND_PAD") (pintype "bidirectional"))
      (node (ref "U7") (pin "4") (pinfunction "GND_4") (pintype "bidirectional"))
      (node (ref "U7") (pin "PAD") (pinfunction "GND_PAD") (pintype "bidirectional"))
      (node (ref "U8") (pin "5") (pinfunction "P$5_5") (pintype "bidirectional"))
    )
    (net (code "43") (name "Net-(C5-Pad2)") (class "Default")
      (node (ref "C5") (pin "2") (pinfunction "2_2") (pintype "passive"))
      (node (ref "R12") (pin "2") (pinfunction "2_2") (pintype "passive"))
    )
    (net (code "44") (name "Net-(D1-PadA)") (class "Default")
      (node (ref "D1") (pin "A") (pinfunction "A_A") (pintype "passive"))
      (node (ref "F1") (pin "1") (pinfunction "1_1") (pintype "bidirectional"))
    )
    (net (code "45") (name "Net-(IC2-PIO0.3)") (class "Default")
      (node (ref "IC2") (pin "9") (pinfunction "PIO0.3_9") (pintype "bidirectional"))
      (node (ref "R25") (pin "2") (pinfunction "2_2") (pintype "passive"))
      (node (ref "R26") (pin "1") (pinfunction "1_1") (pintype "passive"))
    )
    (net (code "46") (name "Net-(IC2-PIO0.6)") (class "Default")
      (node (ref "IC2") (pin "15") (pinfunction "PIO0.6_15") (pintype "bidirectional"))
      (node (ref "Q3") (pin "1") (pinfunction "G_1") (pintype "passive"))
    )
    (net (code "47") (name "Net-(IC2-USB.D+)") (class "Default")
      (node (ref "IC2") (pin "14") (pinfunction "USB.D+_14") (pintype "bidirectional"))
      (node (ref "R27") (pin "2") (pinfunction "2_2") (pintype "passive"))
      (node (ref "R29") (pin "2") (pinfunction "2_2") (pintype "passive"))
    )
    (net (code "48") (name "Net-(IC2-USB.D-)") (class "Default")
      (node (ref "IC2") (pin "13") (pinfunction "USB.D-_13") (pintype "bidirectional"))
      (node (ref "R28") (pin "2") (pinfunction "2_2") (pintype "passive"))
    )
    (net (code "49") (name "Net-(J1--2)") (class "Default")
      (node (ref "J1") (pin "P$2") (pinfunction "-2_P$2") (pintype "bidirectional"))
      (node (ref "J2") (pin "P$2") (pinfunction "-2_P$2") (pintype "bidirectional"))
      (node (ref "J3") (pin "P$2") (pinfunction "-2_P$2") (pintype "bidirectional"))
      (node (ref "Q1") (pin "2") (pinfunction "S_2") (pintype "passive"))
      (node (ref "U4") (pin "2") (pinfunction "V+_2") (pintype "power_in"))
      (node (ref "U4") (pin "4") (pinfunction "-IN_4") (pintype "input"))
    )
    (net (code "50") (name "Net-(J2--3)") (class "Default")
      (node (ref "J2") (pin "P$3") (pinfunction "-3_P$3") (pintype "bidirectional"))
      (node (ref "J3") (pin "P$3") (pinfunction "-3_P$3") (pintype "bidirectional"))
      (node (ref "R16") (pin "2") (pinfunction "2_2") (pintype "passive"))
      (node (ref "R20") (pin "1") (pinfunction "1_1") (pintype "passive"))
    )
    (net (code "51") (name "Net-(J2--4)") (class "Default")
      (node (ref "J2") (pin "P$4") (pinfunction "-4_P$4") (pintype "bidirectional"))
      (node (ref "J3") (pin "P$4") (pinfunction "-4_P$4") (pintype "bidirectional"))
      (node (ref "R17") (pin "2") (pinfunction "2_2") (pintype "passive"))
      (node (ref "SJ4") (pin "1") (pinfunction "1_1") (pintype "passive"))
    )
    (net (code "52") (name "Net-(JP8-VCC)") (class "Default")
      (node (ref "F1") (pin "2") (pinfunction "2_2") (pintype "bidirectional"))
      (node (ref "JP8") (pin "VBUS1") (pinfunction "VCC_VBUS1") (pintype "bidirectional"))
    )
    (net (code "53") (name "Net-(L1-2)") (class "Default")
      (node (ref "D6") (pin "A") (pinfunction "A_A") (pintype "passive"))
      (node (ref "L1") (pin "P$2") (pinfunction "2_P$2") (pintype "passive"))
      (node (ref "U2") (pin "7") (pinfunction "SW_7") (pintype "open_collector"))
      (node (ref "U2") (pin "8") (pinfunction "SW_8") (pintype "open_collector"))
    )
    (net (code "54") (name "Net-(LED1-PadC)") (class "Default")
      (node (ref "LED1") (pin "C") (pinfunction "C_C") (pintype "passive"))
      (node (ref "R19") (pin "1") (pinfunction "1_1") (pintype "passive"))
    )
    (net (code "55") (name "Net-(LED2-PadC)") (class "Default")
      (node (ref "LED2") (pin "C") (pinfunction "C_C") (pintype "passive"))
      (node (ref "R21") (pin "2") (pinfunction "2_2") (pintype "passive"))
    )
    (net (code "56") (name "Net-(LED3-PadC)") (class "Default")
      (node (ref "LED3") (pin "C") (pinfunction "C_C") (pintype "passive"))
      (node (ref "R23") (pin "2") (pinfunction "2_2") (pintype "passive"))
    )
    (net (code "57") (name "Net-(Q1-G)") (class "Default")
      (node (ref "Q1") (pin "1") (pinfunction "G_1") (pintype "passive"))
      (node (ref "U4") (pin "1") (pinfunction "OUT_1") (pintype "output"))
    )
    (net (code "58") (name "Net-(Q3-D)") (class "Default")
      (node (ref "Q3") (pin "3") (pinfunction "D_3") (pintype "passive"))
      (node (ref "R27") (pin "1") (pinfunction "1_1") (pintype "passive"))
    )
    (net (code "59") (name "Net-(R13-Pad2)") (class "Default")
      (node (ref "R13") (pin "2") (pinfunction "2_2") (pintype "passive"))
      (node (ref "SJ2") (pin "2") (pinfunction "2_2") (pintype "passive"))
    )
    (net (code "60") (name "Net-(R14-Pad1)") (class "Default")
      (node (ref "R14") (pin "1") (pinfunction "1_1") (pintype "passive"))
      (node (ref "SJ3") (pin "1") (pinfunction "1_1") (pintype "passive"))
    )
    (net (code "61") (name "Net-(R20-Pad2)") (class "Default")
      (node (ref "R20") (pin "2") (pinfunction "2_2") (pintype "passive"))
      (node (ref "SJ4") (pin "2") (pinfunction "2_2") (pintype "passive"))
    )
    (net (code "62") (name "Net-(SJ1-Pad2)") (class "Default")
      (node (ref "SJ1") (pin "2") (pinfunction "2_2") (pintype "passive"))
      (node (ref "U3") (pin "GPIO0") (pinfunction "GPIO0_GPIO0") (pintype "bidirectional"))
    )
    (net (code "63") (name "Net-(U2-CMP)") (class "Default")
      (node (ref "R12") (pin "1") (pinfunction "1_1") (pintype "passive"))
      (node (ref "U2") (pin "12") (pinfunction "CMP_12") (pintype "passive"))
    )
    (net (code "64") (name "Net-(U2-FB)") (class "Default")
      (node (ref "C6") (pin "1") (pinfunction "1_1") (pintype "passive"))
      (node (ref "R15") (pin "1") (pinfunction "1_1") (pintype "passive"))
      (node (ref "R18") (pin "1") (pinfunction "1_1") (pintype "passive"))
      (node (ref "U2") (pin "3") (pinfunction "FB_3") (pintype "passive"))
    )
    (net (code "65") (name "Net-(U2-SS)") (class "Default")
      (node (ref "C1") (pin "2") (pinfunction "2_2") (pintype "passive"))
      (node (ref "U2") (pin "2") (pinfunction "SS_2") (pintype "passive"))
    )
    (net (code "66") (name "Net-(U5-PROG)") (class "Default")
      (node (ref "R24") (pin "1") (pinfunction "1_1") (pintype "passive"))
      (node (ref "U5") (pin "5") (pinfunction "PROG_5") (pintype "input"))
    )
    (net (code "67") (name "Net-(U5-STAT)") (class "Default")
      (node (ref "R19") (pin "2") (pinfunction "2_2") (pintype "passive"))
      (node (ref "U5") (pin "1") (pinfunction "STAT_1") (pintype "output"))
    )
    (net (code "68") (name "Net-(U6-OUT1)") (class "Default")
      (node (ref "JP5") (pin "1") (pinfunction "1_1") (pintype "passive"))
      (node (ref "U6") (pin "2") (pinfunction "OUT1_2") (pintype "bidirectional"))
    )
    (net (code "69") (name "Net-(U6-OUT2)") (class "Default")
      (node (ref "JP5") (pin "2") (pinfunction "2_2") (pintype "passive"))
      (node (ref "U6") (pin "3") (pinfunction "OUT2_3") (pintype "bidirectional"))
    )
    (net (code "70") (name "Net-(U7-OUT1)") (class "Default")
      (node (ref "JP6") (pin "1") (pinfunction "1_1") (pintype "passive"))
      (node (ref "U7") (pin "2") (pinfunction "OUT1_2") (pintype "bidirectional"))
    )
    (net (code "71") (name "Net-(U7-OUT2)") (class "Default")
      (node (ref "JP6") (pin "2") (pinfunction "2_2") (pintype "passive"))
      (node (ref "U7") (pin "3") (pinfunction "OUT2_3") (pintype "bidirectional"))
    )
    (net (code "72") (name "Net-(U8-P$6)") (class "Default")
      (node (ref "R16") (pin "1") (pinfunction "1_1") (pintype "passive"))
      (node (ref "SJ2") (pin "1") (pinfunction "1_1") (pintype "passive"))
      (node (ref "U8") (pin "6") (pinfunction "P$6_6") (pintype "bidirectional"))
    )
    (net (code "73") (name "Net-(U8-P$7)") (class "Default")
      (node (ref "R17") (pin "1") (pinfunction "1_1") (pintype "passive"))
      (node (ref "SJ3") (pin "2") (pinfunction "2_2") (pintype "passive"))
      (node (ref "U8") (pin "7") (pinfunction "P$7_7") (pintype "bidirectional"))
    )
    (net (code "74") (name "VCC") (class "Default")
      (node (ref "C12") (pin "1") (pinfunction "1_1") (pintype "passive"))
      (node (ref "C3") (pin "2") (pinfunction "2_2") (pintype "passive"))
      (node (ref "J4") (pin "2") (pinfunction "+_2") (pintype "bidirectional"))
      (node (ref "L1") (pin "P$1") (pinfunction "1_P$1") (pintype "passive"))
      (node (ref "Q1") (pin "3") (pinfunction "D_3") (pintype "passive"))
      (node (ref "R30") (pin "2") (pinfunction "2_2") (pintype "passive"))
      (node (ref "U2") (pin "10") (pinfunction "VIN_10") (pintype "passive"))
      (node (ref "U2") (pin "11") (pinfunction "EN_11") (pintype "input"))
      (node (ref "U4") (pin "3") (pinfunction "+IN_3") (pintype "input"))
      (node (ref "U5") (pin "3") (pinfunction "VBAT_3") (pintype "power_in"))
    )
    (net (code "75") (name "VCCIO") (class "Default")
      (node (ref "C21") (pin "2") (pinfunction "2_2") (pintype "passive"))
      (node (ref "C22") (pin "2") (pinfunction "2_2") (pintype "passive"))
      (node (ref "JP1") (pin "1") (pinfunction "1_1") (pintype "passive"))
      (node (ref "JP1") (pin "10") (pinfunction "10_10") (pintype "passive"))
      (node (ref "JP1") (pin "2") (pinfunction "2_2") (pintype "passive"))
      (node (ref "JP1") (pin "3") (pinfunction "3_3") (pintype "passive"))
      (node (ref "JP1") (pin "4") (pinfunction "4_4") (pintype "passive"))
      (node (ref "JP1") (pin "5") (pinfunction "5_5") (pintype "passive"))
      (node (ref "JP1") (pin "6") (pinfunction "6_6") (pintype "passive"))
      (node (ref "JP1") (pin "7") (pinfunction "7_7") (pintype "passive"))
      (node (ref "JP1") (pin "8") (pinfunction "8_8") (pintype "passive"))
      (node (ref "JP1") (pin "9") (pinfunction "9_9") (pintype "passive"))
      (node (ref "S1") (pin "1") (pinfunction "1_1") (pintype "bidirectional"))
      (node (ref "S1") (pin "4") (pinfunction "4_4") (pintype "bidirectional"))
      (node (ref "U6") (pin "1") (pinfunction "VMOT_1") (pintype "bidirectional"))
      (node (ref "U7") (pin "1") (pinfunction "VMOT_1") (pintype "bidirectional"))
    )
    (net (code "76") (name "VNEG") (class "Default")
      (node (ref "C3") (pin "1") (pinfunction "1_1") (pintype "passive"))
      (node (ref "C7") (pin "1") (pinfunction "1_1") (pintype "passive"))
      (node (ref "GND5") (pin "P$1") (pinfunction "P$1_P$1") (pintype "bidirectional"))
      (node (ref "GND6") (pin "P$1") (pinfunction "P$1_P$1") (pintype "bidirectional"))
      (node (ref "U2") (pin "5") (pinfunction "GND_5") (pintype "passive"))
      (node (ref "U2") (pin "6") (pinfunction "GND_6") (pintype "passive"))
    )
    (net (code "77") (name "unconnected-(FUD1-PadP$1)") (class "Default")
      (node (ref "FUD1") (pin "P$1") (pinfunction "P$1_P$1") (pintype "no_connect"))
    )
    (net (code "78") (name "unconnected-(FUD2-PadP$1)") (class "Default")
      (node (ref "FUD2") (pin "P$1") (pinfunction "P$1_P$1") (pintype "no_connect"))
    )
    (net (code "79") (name "unconnected-(FUD3-PadP$1)") (class "Default")
      (node (ref "FUD3") (pin "P$1") (pinfunction "P$1_P$1") (pintype "no_connect"))
    )
    (net (code "80") (name "unconnected-(IC1-NC{slash}ADJ-Pad4)") (class "Default")
      (node (ref "IC1") (pin "4") (pinfunction "NC/ADJ_4") (pintype "bidirectional"))
    )
    (net (code "81") (name "unconnected-(IC2-PIO0.0-Pad2)") (class "Default")
      (node (ref "IC2") (pin "2") (pinfunction "PIO0.0_2") (pintype "bidirectional"))
    )
    (net (code "82") (name "unconnected-(J4-PAD1-PadNC1)") (class "Default")
      (node (ref "J4") (pin "NC1") (pinfunction "PAD1_NC1") (pintype "bidirectional"))
    )
    (net (code "83") (name "unconnected-(J4-PAD2-PadNC2)") (class "Default")
      (node (ref "J4") (pin "NC2") (pinfunction "PAD2_NC2") (pintype "bidirectional"))
    )
    (net (code "84") (name "unconnected-(JP8-ID-PadID1)") (class "Default")
      (node (ref "JP8") (pin "ID1") (pinfunction "ID_ID1") (pintype "bidirectional"))
    )
    (net (code "85") (name "unconnected-(S1-Pad3)") (class "Default")
      (node (ref "S1") (pin "3") (pinfunction "3_3") (pintype "bidirectional"))
    )
    (net (code "86") (name "unconnected-(S1-Pad6)") (class "Default")
      (node (ref "S1") (pin "6") (pinfunction "6_6") (pintype "bidirectional"))
    )
    (net (code "87") (name "unconnected-(U2-NC-Pad1)") (class "Default")
      (node (ref "U2") (pin "1") (pinfunction "NC_1") (pintype "no_connect"))
    )
    (net (code "88") (name "unconnected-(U3-PadANT)") (class "Default")
      (node (ref "U3") (pin "ANT") (pinfunction "ANT_ANT") (pintype "bidirectional"))
    )
    (net (code "89") (name "unconnected-(U3-PadGPIO2)") (class "Default")
      (node (ref "U3") (pin "GPIO2") (pinfunction "GPIO2_GPIO2") (pintype "bidirectional"))
    )
    (net (code "90") (name "unconnected-(U3-PadGPIO12)") (class "Default")
      (node (ref "U3") (pin "GPIO12") (pinfunction "GPIO12_GPIO12") (pintype "bidirectional"))
    )
    (net (code "91") (name "unconnected-(U3-PadGPIO13)") (class "Default")
      (node (ref "U3") (pin "GPIO13") (pinfunction "GPIO13_GPIO13") (pintype "bidirectional"))
    )
    (net (code "92") (name "unconnected-(U3-PadGPIO14)") (class "Default")
      (node (ref "U3") (pin "GPIO14") (pinfunction "GPIO14_GPIO14") (pintype "bidirectional"))
    )
    (net (code "93") (name "unconnected-(U3-PadGPIO18)") (class "Default")
      (node (ref "U3") (pin "GPIO18") (pinfunction "GPIO18_GPIO18") (pintype "bidirectional"))
    )
    (net (code "94") (name "unconnected-(U3-PadNC)") (class "Default")
      (node (ref "U3") (pin "NC") (pinfunction "NC_NC") (pintype "bidirectional"))
    )
  )
)
